# Esquem_tico.net
KiCad netlist of a schematic drawn in Altium Designer
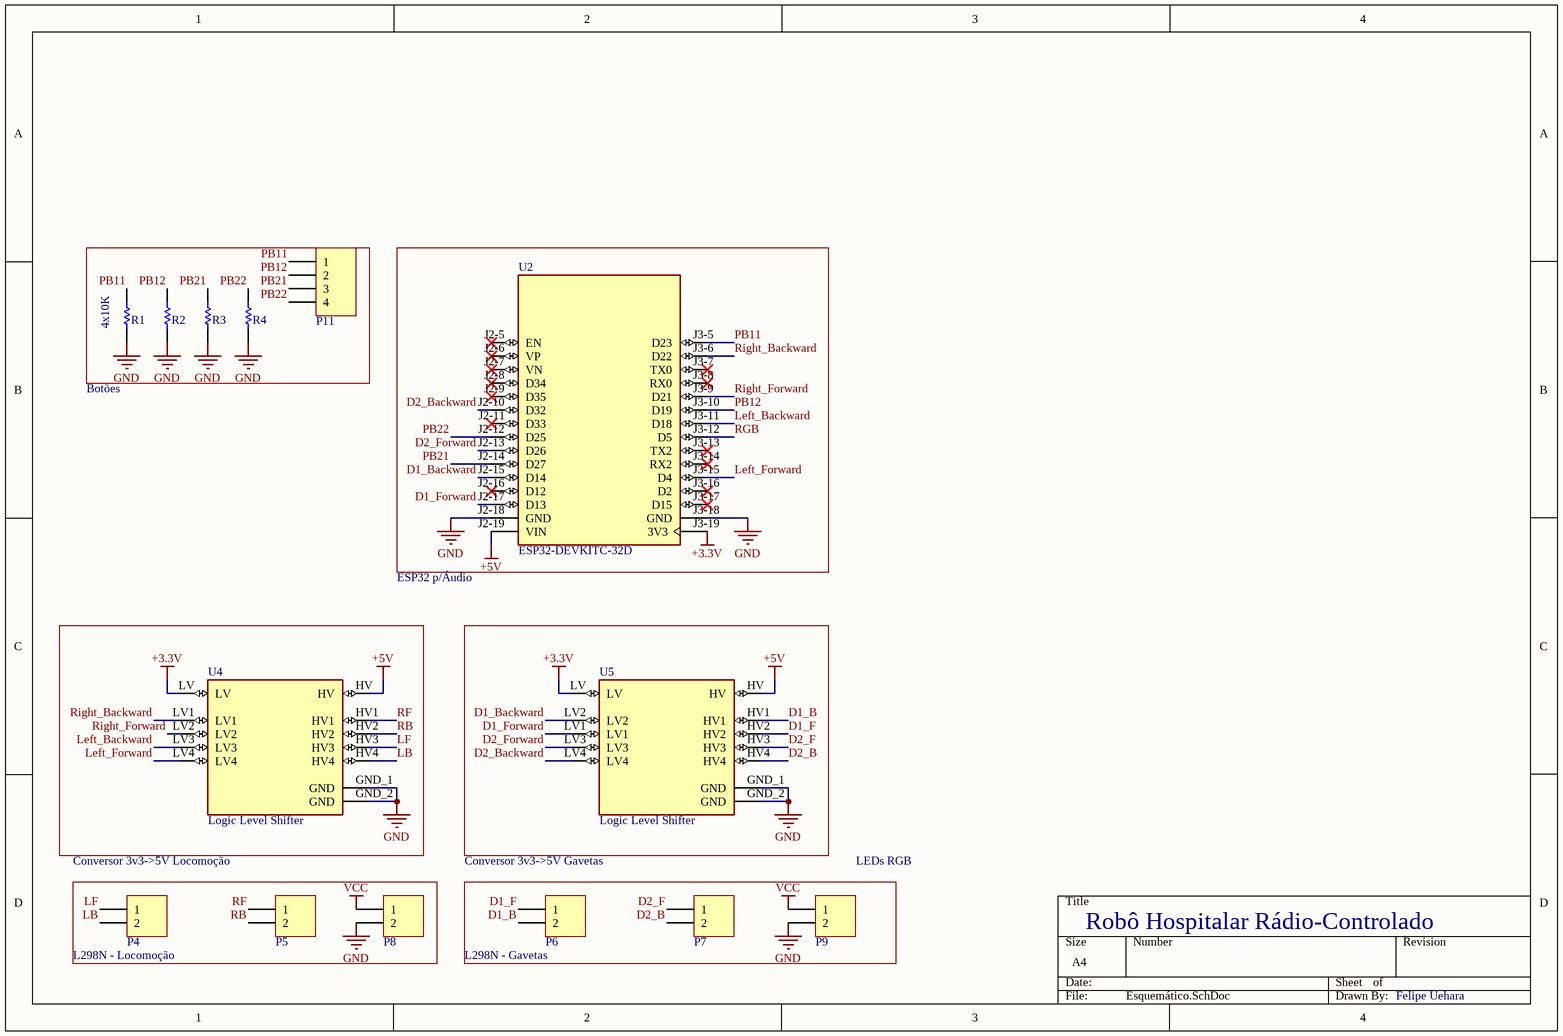
[diagram p0: Esquemático.SchDoc]

(export (version "E")
  (design (tool "Eeschema 10.0.6"))
  (components
    (comp (ref "P4")
      (value "Header 1x2")
      (footprint "KRE1X2")
      (fields (field (name "MANUFACTURER") "Cromax") (field (name "MANUFACTURER PART NUMBER") "IMP10327"))
      (libsource (lib "Schlib1") (part "Header 1x2"))
    )
    (comp (ref "P5")
      (value "Header 1x2")
      (footprint "KRE1X2")
      (fields (field (name "MANUFACTURER") "Cromax") (field (name "MANUFACTURER PART NUMBER") "IMP10327"))
      (libsource (lib "Schlib1") (part "Header 1x2"))
    )
    (comp (ref "P6")
      (value "Header 1x2")
      (footprint "KRE1X2")
      (fields (field (name "MANUFACTURER") "Cromax") (field (name "MANUFACTURER PART NUMBER") "IMP10327"))
      (libsource (lib "Schlib1") (part "Header 1x2"))
    )
    (comp (ref "P7")
      (value "Header 1x2")
      (footprint "KRE1X2")
      (fields (field (name "MANUFACTURER") "Cromax") (field (name "MANUFACTURER PART NUMBER") "IMP10327"))
      (libsource (lib "Schlib1") (part "Header 1x2"))
    )
    (comp (ref "P8")
      (value "Header 1x2")
      (footprint "KRE1X2")
      (fields (field (name "MANUFACTURER") "Cromax") (field (name "MANUFACTURER PART NUMBER") "IMP10327"))
      (libsource (lib "Schlib1") (part "Header 1x2"))
    )
    (comp (ref "P9")
      (value "Header 1x2")
      (footprint "KRE1X2")
      (fields (field (name "MANUFACTURER") "Cromax") (field (name "MANUFACTURER PART NUMBER") "IMP10327"))
      (libsource (lib "Schlib1") (part "Header 1x2"))
    )
    (comp (ref "P11")
      (value "Header 1x4")
      (footprint "HDR1X4")
      (description "Headers & Wire Housings 40Pin 2mm Spacing Single Row Hdrs, 5pc")
      (fields (field (name "MANUFACTURER") "Cromax") (field (name "MANUFACTURER PART NUMBER") "IMP10327"))
      (libsource (lib "Schlib1") (part "Header 1x4"))
    )
    (comp (ref "R1")
      (value "4x10K")
      (footprint "RES 10K 1/4W CARBON FILM")
      (description "RES 10K OHM 1/4W 5% CARBON FILM")
      (fields (field (name "MANUFACTURER") "Ty-Ohm") (field (name "MANUFACTURER PART NUMBER") "CR25"))
      (libsource (lib "Schlib1") (part "RES 10K 1/4W CARBON FILM"))
    )
    (comp (ref "R2")
      (value "RES 10K 1/4W CARBON FILM")
      (footprint "RES 10K 1/4W CARBON FILM")
      (description "RES 10K OHM 1/4W 5% CARBON FILM")
      (fields (field (name "MANUFACTURER") "Ty-Ohm") (field (name "MANUFACTURER PART NUMBER") "CR25"))
      (libsource (lib "Schlib1") (part "RES 10K 1/4W CARBON FILM"))
    )
    (comp (ref "R3")
      (value "RES 10K 1/4W CARBON FILM")
      (footprint "RES 10K 1/4W CARBON FILM")
      (description "RES 10K OHM 1/4W 5% CARBON FILM")
      (fields (field (name "MANUFACTURER") "Ty-Ohm") (field (name "MANUFACTURER PART NUMBER") "CR25"))
      (libsource (lib "Schlib1") (part "RES 10K 1/4W CARBON FILM"))
    )
    (comp (ref "R4")
      (value "RES 10K 1/4W CARBON FILM")
      (footprint "RES 10K 1/4W CARBON FILM")
      (description "RES 10K OHM 1/4W 5% CARBON FILM")
      (fields (field (name "MANUFACTURER") "Ty-Ohm") (field (name "MANUFACTURER PART NUMBER") "CR25"))
      (libsource (lib "Schlib1") (part "RES 10K 1/4W CARBON FILM"))
    )
    (comp (ref "U2")
      (value "ESP32-DEVKITC-32D")
      (footprint "MODULE_ESP32-DEVKITC-32D - duplicate")
      (description "WiFi Development Tools (802.11) ESP32 General Development Kit, ESP32-WROOM-32D on the board")
      (fields (field (name "MF") "Espressif Systems"))
      (libsource (lib "Schlib1") (part "ESP32-DEVKITC-32D"))
    )
    (comp (ref "U4")
      (value "Logic Level Shifter")
      (footprint "CONV_BOB-12009")
      (description "BSS138 - Logic-Level Translator Interface Evaluation Board")
      (fields (field (name "MF") "SparkFun") (field (name "MP") "BOB-12009"))
      (libsource (lib "Schlib1") (part "Logic Level Shifter"))
    )
    (comp (ref "U5")
      (value "Logic Level Shifter")
      (footprint "CONV_BOB-12009")
      (description "BSS138 - Logic-Level Translator Interface Evaluation Board")
      (fields (field (name "MF") "SparkFun") (field (name "MP") "BOB-12009"))
      (libsource (lib "") (part "Logic Level Shifter_1"))
    )
  )
  (nets
    (net (code "1") (name "+3.3V") (class "Default")
      (node (ref "U2") (pin "J3-19") (pinfunction "3V3_J3-19") (pintype "power_in"))
      (node (ref "U4") (pin "LV") (pinfunction "LV_LV") (pintype "bidirectional"))
      (node (ref "U5") (pin "LV") (pinfunction "LV_LV") (pintype "bidirectional"))
    )
    (net (code "2") (name "+5V") (class "Default")
      (node (ref "U2") (pin "J2-19") (pinfunction "VIN_J2-19") (pintype "power_in"))
      (node (ref "U4") (pin "HV") (pinfunction "HV_HV") (pintype "bidirectional"))
      (node (ref "U5") (pin "HV") (pinfunction "HV_HV") (pintype "bidirectional"))
    )
    (net (code "3") (name "/D1_B") (class "Default")
      (node (ref "P6") (pin "2") (pinfunction "2_2") (pintype "passive"))
      (node (ref "U5") (pin "HV1") (pinfunction "HV1_HV1") (pintype "bidirectional"))
    )
    (net (code "4") (name "/D1_Backward") (class "Default")
      (node (ref "U2") (pin "J2-15") (pinfunction "D14_J2-15") (pintype "bidirectional"))
      (node (ref "U5") (pin "LV2") (pinfunction "LV2_LV2") (pintype "bidirectional"))
    )
    (net (code "5") (name "/D1_F") (class "Default")
      (node (ref "P6") (pin "1") (pinfunction "1_1") (pintype "passive"))
      (node (ref "U5") (pin "HV2") (pinfunction "HV2_HV2") (pintype "bidirectional"))
    )
    (net (code "6") (name "/D1_Forward") (class "Default")
      (node (ref "U2") (pin "J2-17") (pinfunction "D13_J2-17") (pintype "bidirectional"))
      (node (ref "U5") (pin "LV1") (pinfunction "LV1_LV1") (pintype "bidirectional"))
    )
    (net (code "7") (name "/D2_B") (class "Default")
      (node (ref "P7") (pin "2") (pinfunction "2_2") (pintype "passive"))
      (node (ref "U5") (pin "HV4") (pinfunction "HV4_HV4") (pintype "bidirectional"))
    )
    (net (code "8") (name "/D2_Backward") (class "Default")
      (node (ref "U2") (pin "J2-10") (pinfunction "D32_J2-10") (pintype "bidirectional"))
      (node (ref "U5") (pin "LV4") (pinfunction "LV4_LV4") (pintype "bidirectional"))
    )
    (net (code "9") (name "/D2_F") (class "Default")
      (node (ref "P7") (pin "1") (pinfunction "1_1") (pintype "passive"))
      (node (ref "U5") (pin "HV3") (pinfunction "HV3_HV3") (pintype "bidirectional"))
    )
    (net (code "10") (name "/D2_Forward") (class "Default")
      (node (ref "U2") (pin "J2-13") (pinfunction "D26_J2-13") (pintype "bidirectional"))
      (node (ref "U5") (pin "LV3") (pinfunction "LV3_LV3") (pintype "bidirectional"))
    )
    (net (code "11") (name "/LB") (class "Default")
      (node (ref "P4") (pin "2") (pinfunction "2_2") (pintype "passive"))
      (node (ref "U4") (pin "HV4") (pinfunction "HV4_HV4") (pintype "bidirectional"))
    )
    (net (code "12") (name "/LF") (class "Default")
      (node (ref "P4") (pin "1") (pinfunction "1_1") (pintype "passive"))
      (node (ref "U4") (pin "HV3") (pinfunction "HV3_HV3") (pintype "bidirectional"))
    )
    (net (code "13") (name "/Left_Backward") (class "Default")
      (node (ref "U2") (pin "J3-11") (pinfunction "D18_J3-11") (pintype "bidirectional"))
      (node (ref "U4") (pin "LV3") (pinfunction "LV3_LV3") (pintype "bidirectional"))
    )
    (net (code "14") (name "/Left_Forward") (class "Default")
      (node (ref "U2") (pin "J3-15") (pinfunction "D4_J3-15") (pintype "bidirectional"))
      (node (ref "U4") (pin "LV4") (pinfunction "LV4_LV4") (pintype "bidirectional"))
    )
    (net (code "15") (name "/PB11") (class "Default")
      (node (ref "P11") (pin "1") (pinfunction "1_1") (pintype "passive"))
      (node (ref "R1") (pin "2") (pinfunction "2_2") (pintype "passive"))
      (node (ref "U2") (pin "J3-5") (pinfunction "D23_J3-5") (pintype "bidirectional"))
    )
    (net (code "16") (name "/PB12") (class "Default")
      (node (ref "P11") (pin "2") (pinfunction "2_2") (pintype "passive"))
      (node (ref "R2") (pin "2") (pinfunction "2_2") (pintype "passive"))
      (node (ref "U2") (pin "J3-10") (pinfunction "D19_J3-10") (pintype "bidirectional"))
    )
    (net (code "17") (name "/PB21") (class "Default")
      (node (ref "P11") (pin "3") (pinfunction "3_3") (pintype "power_in"))
      (node (ref "R3") (pin "2") (pinfunction "2_2") (pintype "passive"))
      (node (ref "U2") (pin "J2-14") (pinfunction "D27_J2-14") (pintype "bidirectional"))
    )
    (net (code "18") (name "/PB22") (class "Default")
      (node (ref "P11") (pin "4") (pinfunction "4_4") (pintype "power_in"))
      (node (ref "R4") (pin "2") (pinfunction "2_2") (pintype "passive"))
      (node (ref "U2") (pin "J2-12") (pinfunction "D25_J2-12") (pintype "bidirectional"))
    )
    (net (code "19") (name "/RB") (class "Default")
      (node (ref "P5") (pin "2") (pinfunction "2_2") (pintype "passive"))
      (node (ref "U4") (pin "HV2") (pinfunction "HV2_HV2") (pintype "bidirectional"))
    )
    (net (code "20") (name "/RF") (class "Default")
      (node (ref "P5") (pin "1") (pinfunction "1_1") (pintype "passive"))
      (node (ref "U4") (pin "HV1") (pinfunction "HV1_HV1") (pintype "bidirectional"))
    )
    (net (code "21") (name "/RGB") (class "Default")
      (node (ref "U2") (pin "J3-12") (pinfunction "D5_J3-12") (pintype "bidirectional"))
    )
    (net (code "22") (name "/Right_Backward") (class "Default")
      (node (ref "U2") (pin "J3-6") (pinfunction "D22_J3-6") (pintype "bidirectional"))
      (node (ref "U4") (pin "LV1") (pinfunction "LV1_LV1") (pintype "bidirectional"))
    )
    (net (code "23") (name "/Right_Forward") (class "Default")
      (node (ref "U2") (pin "J3-9") (pinfunction "D21_J3-9") (pintype "bidirectional"))
      (node (ref "U4") (pin "LV2") (pinfunction "LV2_LV2") (pintype "bidirectional"))
    )
    (net (code "24") (name "GND") (class "Default")
      (node (ref "P8") (pin "2") (pinfunction "2_2") (pintype "passive"))
      (node (ref "P9") (pin "2") (pinfunction "2_2") (pintype "passive"))
      (node (ref "R1") (pin "1") (pinfunction "1_1") (pintype "passive"))
      (node (ref "R2") (pin "1") (pinfunction "1_1") (pintype "passive"))
      (node (ref "R3") (pin "1") (pinfunction "1_1") (pintype "passive"))
      (node (ref "R4") (pin "1") (pinfunction "1_1") (pintype "passive"))
      (node (ref "U2") (pin "J2-18") (pinfunction "GND_J2-18") (pintype "power_in"))
      (node (ref "U2") (pin "J3-18") (pinfunction "GND_J3-18") (pintype "power_in"))
      (node (ref "U4") (pin "GND_1") (pinfunction "GND_GND_1") (pintype "power_in"))
      (node (ref "U4") (pin "GND_2") (pinfunction "GND_GND_2") (pintype "power_in"))
      (node (ref "U5") (pin "GND_1") (pinfunction "GND_GND_1") (pintype "power_in"))
      (node (ref "U5") (pin "GND_2") (pinfunction "GND_GND_2") (pintype "power_in"))
    )
    (net (code "25") (name "VCC") (class "Default")
      (node (ref "P8") (pin "1") (pinfunction "1_1") (pintype "passive"))
      (node (ref "P9") (pin "1") (pinfunction "1_1") (pintype "passive"))
    )
    (net (code "26") (name "unconnected-(U2-D2-PadJ3-16)") (class "Default")
      (node (ref "U2") (pin "J3-16") (pinfunction "D2_J3-16") (pintype "bidirectional+no_connect"))
    )
    (net (code "27") (name "unconnected-(U2-D12-PadJ2-16)") (class "Default")
      (node (ref "U2") (pin "J2-16") (pinfunction "D12_J2-16") (pintype "bidirectional+no_connect"))
    )
    (net (code "28") (name "unconnected-(U2-D15-PadJ3-17)") (class "Default")
      (node (ref "U2") (pin "J3-17") (pinfunction "D15_J3-17") (pintype "bidirectional+no_connect"))
    )
    (net (code "29") (name "unconnected-(U2-D33-PadJ2-11)") (class "Default")
      (node (ref "U2") (pin "J2-11") (pinfunction "D33_J2-11") (pintype "bidirectional+no_connect"))
    )
    (net (code "30") (name "unconnected-(U2-D34-PadJ2-8)") (class "Default")
      (node (ref "U2") (pin "J2-8") (pinfunction "D34_J2-8") (pintype "bidirectional+no_connect"))
    )
    (net (code "31") (name "unconnected-(U2-D35-PadJ2-9)") (class "Default")
      (node (ref "U2") (pin "J2-9") (pinfunction "D35_J2-9") (pintype "bidirectional+no_connect"))
    )
    (net (code "32") (name "unconnected-(U2-EN-PadJ2-5)") (class "Default")
      (node (ref "U2") (pin "J2-5") (pinfunction "EN_J2-5") (pintype "bidirectional+no_connect"))
    )
    (net (code "33") (name "unconnected-(U2-RX0-PadJ3-8)") (class "Default")
      (node (ref "U2") (pin "J3-8") (pinfunction "RX0_J3-8") (pintype "bidirectional+no_connect"))
    )
    (net (code "34") (name "unconnected-(U2-RX2-PadJ3-14)") (class "Default")
      (node (ref "U2") (pin "J3-14") (pinfunction "RX2_J3-14") (pintype "bidirectional+no_connect"))
    )
    (net (code "35") (name "unconnected-(U2-TX0-PadJ3-7)") (class "Default")
      (node (ref "U2") (pin "J3-7") (pinfunction "TX0_J3-7") (pintype "bidirectional+no_connect"))
    )
    (net (code "36") (name "unconnected-(U2-TX2-PadJ3-13)") (class "Default")
      (node (ref "U2") (pin "J3-13") (pinfunction "TX2_J3-13") (pintype "bidirectional+no_connect"))
    )
    (net (code "37") (name "unconnected-(U2-VN-PadJ2-7)") (class "Default")
      (node (ref "U2") (pin "J2-7") (pinfunction "VN_J2-7") (pintype "bidirectional+no_connect"))
    )
    (net (code "38") (name "unconnected-(U2-VP-PadJ2-6)") (class "Default")
      (node (ref "U2") (pin "J2-6") (pinfunction "VP_J2-6") (pintype "bidirectional+no_connect"))
    )
  )
)
